# 11_RK3588_MIPI_D_C_PHY0_1.net
KiCad netlist of a schematic drawn in Altium Designer
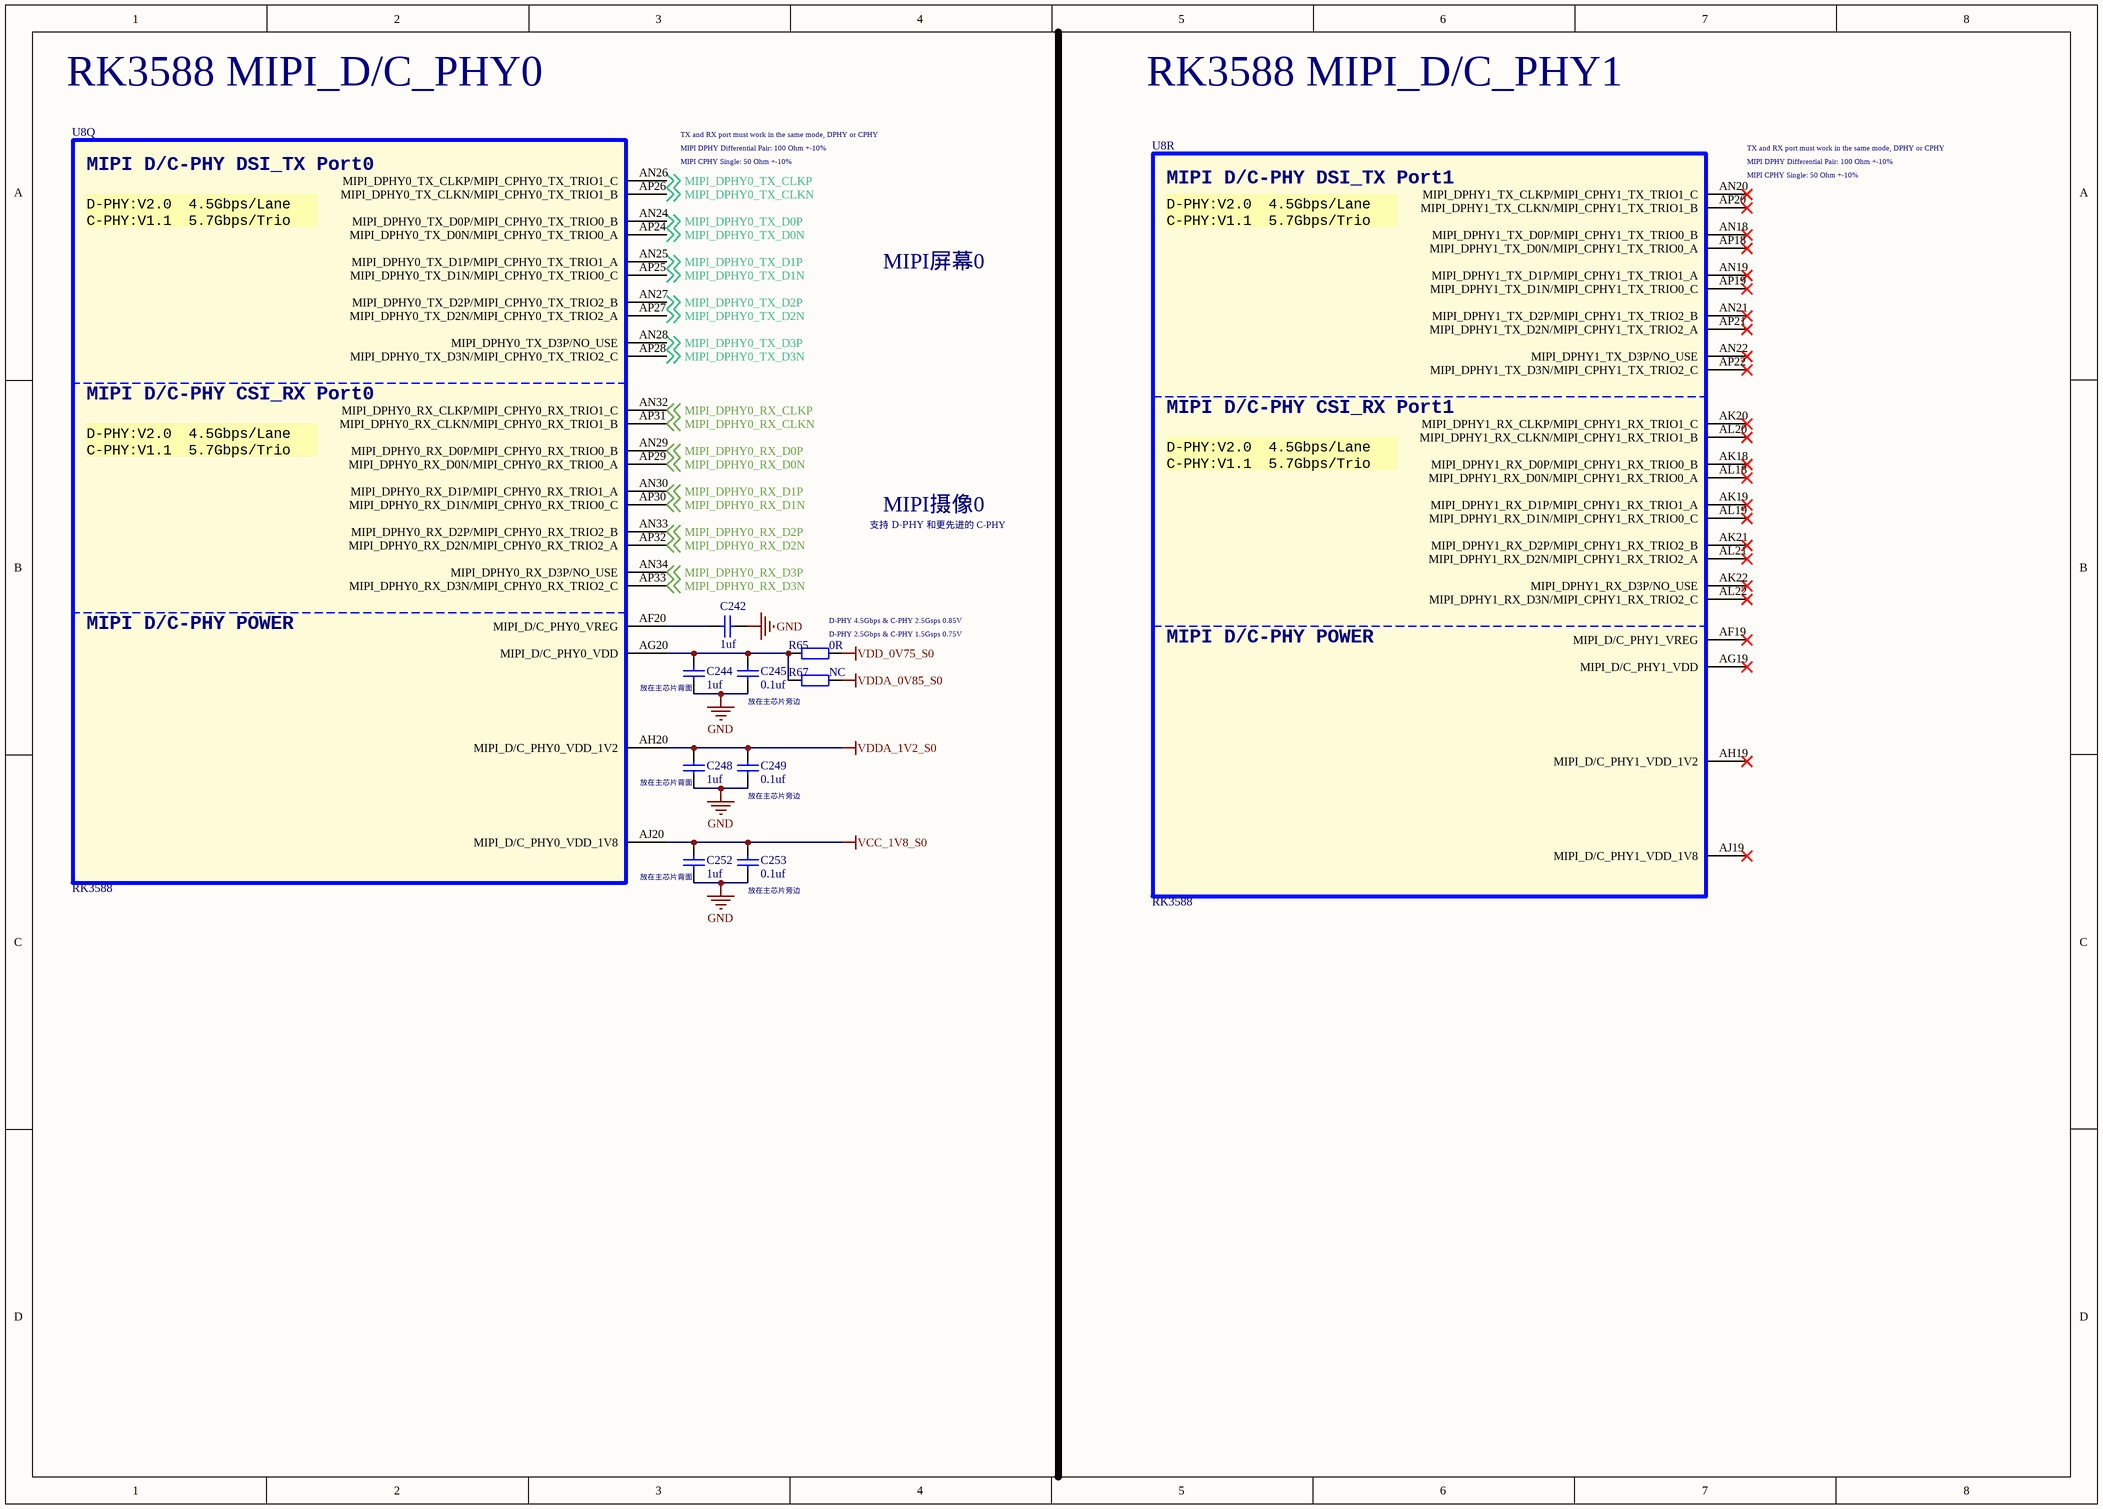
[diagram p0: 11.RK3588_MIPI_D_C_PHY0_1.SchDoc]

(export (version "E")
  (design (tool "Eeschema 10.0.6"))
  (components
    (comp (ref "C242")
      (value "1uf")
      (footprint "0.PCB1:C0201_L")
      (description "贴片电容/MLCC电容")
      (libsource (lib "RK3588") (part "C"))
    )
    (comp (ref "C244")
      (value "1uf")
      (footprint "0.PCB1:C0201_L")
      (description "贴片电容/MLCC电容")
      (libsource (lib "RK3588") (part "C"))
    )
    (comp (ref "C245")
      (value "0.1uf")
      (footprint "0.PCB1:C0201_L")
      (description "贴片电容/MLCC电容")
      (libsource (lib "RK3588") (part "C"))
    )
    (comp (ref "C248")
      (value "1uf")
      (footprint "0.PCB1:C0201_L")
      (description "贴片电容/MLCC电容")
      (libsource (lib "RK3588") (part "C"))
    )
    (comp (ref "C249")
      (value "0.1uf")
      (footprint "0.PCB1:C0201_L")
      (description "贴片电容/MLCC电容")
      (libsource (lib "RK3588") (part "C"))
    )
    (comp (ref "C252")
      (value "1uf")
      (footprint "0.PCB1:C0201_L")
      (description "贴片电容/MLCC电容")
      (libsource (lib "RK3588") (part "C"))
    )
    (comp (ref "C253")
      (value "0.1uf")
      (footprint "0.PCB1:C0201_L")
      (description "贴片电容/MLCC电容")
      (libsource (lib "RK3588") (part "C"))
    )
    (comp (ref "R65")
      (value "0R")
      (footprint "0.PCB1:R0402_L")
      (description "贴片电阻")
      (libsource (lib "RK3588") (part "R"))
    )
    (comp (ref "R67")
      (value "NC")
      (footprint "0.PCB1:R0402_L")
      (description "贴片电阻")
      (libsource (lib "RK3588") (part "R"))
    )
    (comp (ref "U8")
      (value "RK3588")
      (footprint "0.PCB1:BGA1088_23R00X23R00X2R00")
      (description "ROCKCHIP SOC")
      (libsource (lib "RK3588") (part "SOC_RK3588"))
    )
  )
  (nets
    (net (code "1") (name "GND") (class "Default")
      (node (ref "C242") (pin "2") (pinfunction "2_2") (pintype "passive"))
      (node (ref "C244") (pin "1") (pinfunction "1_1") (pintype "passive"))
      (node (ref "C245") (pin "1") (pinfunction "1_1") (pintype "passive"))
      (node (ref "C248") (pin "1") (pinfunction "1_1") (pintype "passive"))
      (node (ref "C249") (pin "1") (pinfunction "1_1") (pintype "passive"))
      (node (ref "C252") (pin "1") (pinfunction "1_1") (pintype "passive"))
      (node (ref "C253") (pin "1") (pinfunction "1_1") (pintype "passive"))
    )
    (net (code "2") (name "MIPI_DPHY0_RX_CLKN") (class "Default")
      (node (ref "U8") (pin "AP31") (pinfunction "MIPI_DPHY0_RX_CLKN/MIPI_CPHY0_RX_TRIO1_B_AP31") (pintype "passive"))
    )
    (net (code "3") (name "MIPI_DPHY0_RX_CLKP") (class "Default")
      (node (ref "U8") (pin "AN32") (pinfunction "MIPI_DPHY0_RX_CLKP/MIPI_CPHY0_RX_TRIO1_C_AN32") (pintype "passive"))
    )
    (net (code "4") (name "MIPI_DPHY0_RX_D0N") (class "Default")
      (node (ref "U8") (pin "AP29") (pinfunction "MIPI_DPHY0_RX_D0N/MIPI_CPHY0_RX_TRIO0_A_AP29") (pintype "passive"))
    )
    (net (code "5") (name "MIPI_DPHY0_RX_D0P") (class "Default")
      (node (ref "U8") (pin "AN29") (pinfunction "MIPI_DPHY0_RX_D0P/MIPI_CPHY0_RX_TRIO0_B_AN29") (pintype "passive"))
    )
    (net (code "6") (name "MIPI_DPHY0_RX_D1N") (class "Default")
      (node (ref "U8") (pin "AP30") (pinfunction "MIPI_DPHY0_RX_D1N/MIPI_CPHY0_RX_TRIO0_C_AP30") (pintype "passive"))
    )
    (net (code "7") (name "MIPI_DPHY0_RX_D1P") (class "Default")
      (node (ref "U8") (pin "AN30") (pinfunction "MIPI_DPHY0_RX_D1P/MIPI_CPHY0_RX_TRIO1_A_AN30") (pintype "passive"))
    )
    (net (code "8") (name "MIPI_DPHY0_RX_D2N") (class "Default")
      (node (ref "U8") (pin "AP32") (pinfunction "MIPI_DPHY0_RX_D2N/MIPI_CPHY0_RX_TRIO2_A_AP32") (pintype "passive"))
    )
    (net (code "9") (name "MIPI_DPHY0_RX_D2P") (class "Default")
      (node (ref "U8") (pin "AN33") (pinfunction "MIPI_DPHY0_RX_D2P/MIPI_CPHY0_RX_TRIO2_B_AN33") (pintype "passive"))
    )
    (net (code "10") (name "MIPI_DPHY0_RX_D3N") (class "Default")
      (node (ref "U8") (pin "AP33") (pinfunction "MIPI_DPHY0_RX_D3N/MIPI_CPHY0_RX_TRIO2_C_AP33") (pintype "passive"))
    )
    (net (code "11") (name "MIPI_DPHY0_RX_D3P") (class "Default")
      (node (ref "U8") (pin "AN34") (pinfunction "MIPI_DPHY0_RX_D3P/NO_USE_AN34") (pintype "passive"))
    )
    (net (code "12") (name "MIPI_DPHY0_TX_CLKN") (class "Default")
      (node (ref "U8") (pin "AP26") (pinfunction "MIPI_DPHY0_TX_CLKN/MIPI_CPHY0_TX_TRIO1_B_AP26") (pintype "passive"))
    )
    (net (code "13") (name "MIPI_DPHY0_TX_CLKP") (class "Default")
      (node (ref "U8") (pin "AN26") (pinfunction "MIPI_DPHY0_TX_CLKP/MIPI_CPHY0_TX_TRIO1_C_AN26") (pintype "passive"))
    )
    (net (code "14") (name "MIPI_DPHY0_TX_D0N") (class "Default")
      (node (ref "U8") (pin "AP24") (pinfunction "MIPI_DPHY0_TX_D0N/MIPI_CPHY0_TX_TRIO0_A_AP24") (pintype "passive"))
    )
    (net (code "15") (name "MIPI_DPHY0_TX_D0P") (class "Default")
      (node (ref "U8") (pin "AN24") (pinfunction "MIPI_DPHY0_TX_D0P/MIPI_CPHY0_TX_TRIO0_B_AN24") (pintype "passive"))
    )
    (net (code "16") (name "MIPI_DPHY0_TX_D1N") (class "Default")
      (node (ref "U8") (pin "AP25") (pinfunction "MIPI_DPHY0_TX_D1N/MIPI_CPHY0_TX_TRIO0_C_AP25") (pintype "passive"))
    )
    (net (code "17") (name "MIPI_DPHY0_TX_D1P") (class "Default")
      (node (ref "U8") (pin "AN25") (pinfunction "MIPI_DPHY0_TX_D1P/MIPI_CPHY0_TX_TRIO1_A_AN25") (pintype "passive"))
    )
    (net (code "18") (name "MIPI_DPHY0_TX_D2N") (class "Default")
      (node (ref "U8") (pin "AP27") (pinfunction "MIPI_DPHY0_TX_D2N/MIPI_CPHY0_TX_TRIO2_A_AP27") (pintype "passive"))
    )
    (net (code "19") (name "MIPI_DPHY0_TX_D2P") (class "Default")
      (node (ref "U8") (pin "AN27") (pinfunction "MIPI_DPHY0_TX_D2P/MIPI_CPHY0_TX_TRIO2_B_AN27") (pintype "passive"))
    )
    (net (code "20") (name "MIPI_DPHY0_TX_D3N") (class "Default")
      (node (ref "U8") (pin "AP28") (pinfunction "MIPI_DPHY0_TX_D3N/MIPI_CPHY0_TX_TRIO2_C_AP28") (pintype "passive"))
    )
    (net (code "21") (name "MIPI_DPHY0_TX_D3P") (class "Default")
      (node (ref "U8") (pin "AN28") (pinfunction "MIPI_DPHY0_TX_D3P/NO_USE_AN28") (pintype "passive"))
    )
    (net (code "22") (name "Net-(U8Q-MIPI_D{slash}C_PHY0_VDD)") (class "Default")
      (node (ref "C244") (pin "2") (pinfunction "2_2") (pintype "passive"))
      (node (ref "C245") (pin "2") (pinfunction "2_2") (pintype "passive"))
      (node (ref "R65") (pin "1") (pinfunction "1_1") (pintype "passive"))
      (node (ref "R67") (pin "1") (pinfunction "1_1") (pintype "passive"))
      (node (ref "U8") (pin "AG20") (pinfunction "MIPI_D/C_PHY0_VDD_AG20") (pintype "passive"))
    )
    (net (code "23") (name "Net-(U8Q-MIPI_D{slash}C_PHY0_VREG)") (class "Default")
      (node (ref "C242") (pin "1") (pinfunction "1_1") (pintype "passive"))
      (node (ref "U8") (pin "AF20") (pinfunction "MIPI_D/C_PHY0_VREG_AF20") (pintype "passive"))
    )
    (net (code "24") (name "VCC_1V8_S0") (class "Default")
      (node (ref "C252") (pin "2") (pinfunction "2_2") (pintype "passive"))
      (node (ref "C253") (pin "2") (pinfunction "2_2") (pintype "passive"))
      (node (ref "U8") (pin "AJ20") (pinfunction "MIPI_D/C_PHY0_VDD_1V8_AJ20") (pintype "passive"))
    )
    (net (code "25") (name "VDDA_0V85_S0") (class "Default")
      (node (ref "R67") (pin "2") (pinfunction "2_2") (pintype "passive"))
    )
    (net (code "26") (name "VDDA_1V2_S0") (class "Default")
      (node (ref "C248") (pin "2") (pinfunction "2_2") (pintype "passive"))
      (node (ref "C249") (pin "2") (pinfunction "2_2") (pintype "passive"))
      (node (ref "U8") (pin "AH20") (pinfunction "MIPI_D/C_PHY0_VDD_1V2_AH20") (pintype "passive"))
    )
    (net (code "27") (name "VDD_0V75_S0") (class "Default")
      (node (ref "R65") (pin "2") (pinfunction "2_2") (pintype "passive"))
    )
    (net (code "28") (name "unconnected-(U8R-MIPI_DPHY1_RX_CLKN{slash}MIPI_CPHY1_RX_TRIO1_B-PadAL20)") (class "Default")
      (node (ref "U8") (pin "AL20") (pinfunction "MIPI_DPHY1_RX_CLKN/MIPI_CPHY1_RX_TRIO1_B_AL20") (pintype "passive+no_connect"))
    )
    (net (code "29") (name "unconnected-(U8R-MIPI_DPHY1_RX_CLKP{slash}MIPI_CPHY1_RX_TRIO1_C-PadAK20)") (class "Default")
      (node (ref "U8") (pin "AK20") (pinfunction "MIPI_DPHY1_RX_CLKP/MIPI_CPHY1_RX_TRIO1_C_AK20") (pintype "passive+no_connect"))
    )
    (net (code "30") (name "unconnected-(U8R-MIPI_DPHY1_RX_D0N{slash}MIPI_CPHY1_RX_TRIO0_A-PadAL18)") (class "Default")
      (node (ref "U8") (pin "AL18") (pinfunction "MIPI_DPHY1_RX_D0N/MIPI_CPHY1_RX_TRIO0_A_AL18") (pintype "passive+no_connect"))
    )
    (net (code "31") (name "unconnected-(U8R-MIPI_DPHY1_RX_D0P{slash}MIPI_CPHY1_RX_TRIO0_B-PadAK18)") (class "Default")
      (node (ref "U8") (pin "AK18") (pinfunction "MIPI_DPHY1_RX_D0P/MIPI_CPHY1_RX_TRIO0_B_AK18") (pintype "passive+no_connect"))
    )
    (net (code "32") (name "unconnected-(U8R-MIPI_DPHY1_RX_D1N{slash}MIPI_CPHY1_RX_TRIO0_C-PadAL19)") (class "Default")
      (node (ref "U8") (pin "AL19") (pinfunction "MIPI_DPHY1_RX_D1N/MIPI_CPHY1_RX_TRIO0_C_AL19") (pintype "passive+no_connect"))
    )
    (net (code "33") (name "unconnected-(U8R-MIPI_DPHY1_RX_D1P{slash}MIPI_CPHY1_RX_TRIO1_A-PadAK19)") (class "Default")
      (node (ref "U8") (pin "AK19") (pinfunction "MIPI_DPHY1_RX_D1P/MIPI_CPHY1_RX_TRIO1_A_AK19") (pintype "passive+no_connect"))
    )
    (net (code "34") (name "unconnected-(U8R-MIPI_DPHY1_RX_D2N{slash}MIPI_CPHY1_RX_TRIO2_A-PadAL21)") (class "Default")
      (node (ref "U8") (pin "AL21") (pinfunction "MIPI_DPHY1_RX_D2N/MIPI_CPHY1_RX_TRIO2_A_AL21") (pintype "passive+no_connect"))
    )
    (net (code "35") (name "unconnected-(U8R-MIPI_DPHY1_RX_D2P{slash}MIPI_CPHY1_RX_TRIO2_B-PadAK21)") (class "Default")
      (node (ref "U8") (pin "AK21") (pinfunction "MIPI_DPHY1_RX_D2P/MIPI_CPHY1_RX_TRIO2_B_AK21") (pintype "passive+no_connect"))
    )
    (net (code "36") (name "unconnected-(U8R-MIPI_DPHY1_RX_D3N{slash}MIPI_CPHY1_RX_TRIO2_C-PadAL22)") (class "Default")
      (node (ref "U8") (pin "AL22") (pinfunction "MIPI_DPHY1_RX_D3N/MIPI_CPHY1_RX_TRIO2_C_AL22") (pintype "passive+no_connect"))
    )
    (net (code "37") (name "unconnected-(U8R-MIPI_DPHY1_RX_D3P{slash}NO_USE-PadAK22)") (class "Default")
      (node (ref "U8") (pin "AK22") (pinfunction "MIPI_DPHY1_RX_D3P/NO_USE_AK22") (pintype "passive+no_connect"))
    )
    (net (code "38") (name "unconnected-(U8R-MIPI_DPHY1_TX_CLKN{slash}MIPI_CPHY1_TX_TRIO1_B-PadAP20)") (class "Default")
      (node (ref "U8") (pin "AP20") (pinfunction "MIPI_DPHY1_TX_CLKN/MIPI_CPHY1_TX_TRIO1_B_AP20") (pintype "passive+no_connect"))
    )
    (net (code "39") (name "unconnected-(U8R-MIPI_DPHY1_TX_CLKP{slash}MIPI_CPHY1_TX_TRIO1_C-PadAN20)") (class "Default")
      (node (ref "U8") (pin "AN20") (pinfunction "MIPI_DPHY1_TX_CLKP/MIPI_CPHY1_TX_TRIO1_C_AN20") (pintype "passive+no_connect"))
    )
    (net (code "40") (name "unconnected-(U8R-MIPI_DPHY1_TX_D0N{slash}MIPI_CPHY1_TX_TRIO0_A-PadAP18)") (class "Default")
      (node (ref "U8") (pin "AP18") (pinfunction "MIPI_DPHY1_TX_D0N/MIPI_CPHY1_TX_TRIO0_A_AP18") (pintype "passive+no_connect"))
    )
    (net (code "41") (name "unconnected-(U8R-MIPI_DPHY1_TX_D0P{slash}MIPI_CPHY1_TX_TRIO0_B-PadAN18)") (class "Default")
      (node (ref "U8") (pin "AN18") (pinfunction "MIPI_DPHY1_TX_D0P/MIPI_CPHY1_TX_TRIO0_B_AN18") (pintype "passive+no_connect"))
    )
    (net (code "42") (name "unconnected-(U8R-MIPI_DPHY1_TX_D1N{slash}MIPI_CPHY1_TX_TRIO0_C-PadAP19)") (class "Default")
      (node (ref "U8") (pin "AP19") (pinfunction "MIPI_DPHY1_TX_D1N/MIPI_CPHY1_TX_TRIO0_C_AP19") (pintype "passive+no_connect"))
    )
    (net (code "43") (name "unconnected-(U8R-MIPI_DPHY1_TX_D1P{slash}MIPI_CPHY1_TX_TRIO1_A-PadAN19)") (class "Default")
      (node (ref "U8") (pin "AN19") (pinfunction "MIPI_DPHY1_TX_D1P/MIPI_CPHY1_TX_TRIO1_A_AN19") (pintype "passive+no_connect"))
    )
    (net (code "44") (name "unconnected-(U8R-MIPI_DPHY1_TX_D2N{slash}MIPI_CPHY1_TX_TRIO2_A-PadAP21)") (class "Default")
      (node (ref "U8") (pin "AP21") (pinfunction "MIPI_DPHY1_TX_D2N/MIPI_CPHY1_TX_TRIO2_A_AP21") (pintype "passive+no_connect"))
    )
    (net (code "45") (name "unconnected-(U8R-MIPI_DPHY1_TX_D2P{slash}MIPI_CPHY1_TX_TRIO2_B-PadAN21)") (class "Default")
      (node (ref "U8") (pin "AN21") (pinfunction "MIPI_DPHY1_TX_D2P/MIPI_CPHY1_TX_TRIO2_B_AN21") (pintype "passive+no_connect"))
    )
    (net (code "46") (name "unconnected-(U8R-MIPI_DPHY1_TX_D3N{slash}MIPI_CPHY1_TX_TRIO2_C-PadAP22)") (class "Default")
      (node (ref "U8") (pin "AP22") (pinfunction "MIPI_DPHY1_TX_D3N/MIPI_CPHY1_TX_TRIO2_C_AP22") (pintype "passive+no_connect"))
    )
    (net (code "47") (name "unconnected-(U8R-MIPI_DPHY1_TX_D3P{slash}NO_USE-PadAN22)") (class "Default")
      (node (ref "U8") (pin "AN22") (pinfunction "MIPI_DPHY1_TX_D3P/NO_USE_AN22") (pintype "passive+no_connect"))
    )
    (net (code "48") (name "unconnected-(U8R-MIPI_D{slash}C_PHY1_VDD-PadAG19)") (class "Default")
      (node (ref "U8") (pin "AG19") (pinfunction "MIPI_D/C_PHY1_VDD_AG19") (pintype "passive+no_connect"))
    )
    (net (code "49") (name "unconnected-(U8R-MIPI_D{slash}C_PHY1_VDD_1V2-PadAH19)") (class "Default")
      (node (ref "U8") (pin "AH19") (pinfunction "MIPI_D/C_PHY1_VDD_1V2_AH19") (pintype "passive+no_connect"))
    )
    (net (code "50") (name "unconnected-(U8R-MIPI_D{slash}C_PHY1_VDD_1V8-PadAJ19)") (class "Default")
      (node (ref "U8") (pin "AJ19") (pinfunction "MIPI_D/C_PHY1_VDD_1V8_AJ19") (pintype "passive+no_connect"))
    )
    (net (code "51") (name "unconnected-(U8R-MIPI_D{slash}C_PHY1_VREG-PadAF19)") (class "Default")
      (node (ref "U8") (pin "AF19") (pinfunction "MIPI_D/C_PHY1_VREG_AF19") (pintype "passive+no_connect"))
    )
  )
)
